# dual-h-bridge.net
KiCad netlist of a schematic drawn in EAGLE
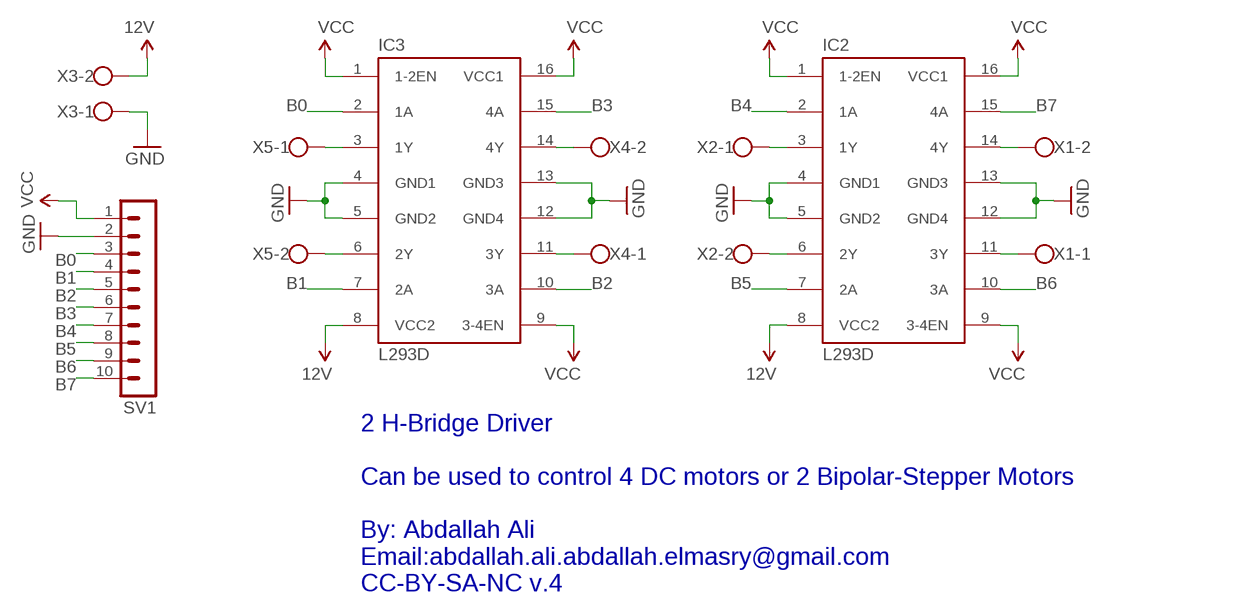
[diagram p0: schematic, sheet 1]

(export (version "E")
  (design (tool "Eeschema 10.0.6"))
  (components
    (comp (ref "IC2")
      (value "L293D")
      (footprint "eagle-import:DIL16")
      (libsource (lib "eagle-import") (part "L293D"))
    )
    (comp (ref "IC3")
      (value "L293D")
      (footprint "eagle-import:DIL16")
      (libsource (lib "eagle-import") (part "L293D"))
    )
    (comp (ref "SV1")
      (value "MA10-1")
      (footprint "eagle-import:MA10-1")
      (libsource (lib "eagle-import") (part "MA10-1"))
    )
    (comp (ref "X1")
      (value "W237-102")
      (footprint "eagle-import:W237-102")
      (fields (field (name "MPN") "237-102"))
      (libsource (lib "eagle-import") (part "W237-102"))
    )
    (comp (ref "X2")
      (value "W237-102")
      (footprint "eagle-import:W237-102")
      (fields (field (name "MPN") "237-102"))
      (libsource (lib "eagle-import") (part "W237-102"))
    )
    (comp (ref "X3")
      (value "W237-102")
      (footprint "eagle-import:W237-102")
      (fields (field (name "MPN") "237-102"))
      (libsource (lib "eagle-import") (part "W237-102"))
    )
    (comp (ref "X4")
      (value "W237-102")
      (footprint "eagle-import:W237-102")
      (fields (field (name "MPN") "237-102"))
      (libsource (lib "eagle-import") (part "W237-102"))
    )
    (comp (ref "X5")
      (value "W237-102")
      (footprint "eagle-import:W237-102")
      (fields (field (name "MPN") "237-102"))
      (libsource (lib "eagle-import") (part "W237-102"))
    )
  )
  (nets
    (net (code "1") (name "/B0") (class "Default")
      (node (ref "IC3") (pin "2") (pinfunction "1A_2") (pintype "input"))
      (node (ref "SV1") (pin "3") (pinfunction "3_3") (pintype "passive"))
    )
    (net (code "2") (name "/B1") (class "Default")
      (node (ref "IC3") (pin "7") (pinfunction "2A_7") (pintype "input"))
      (node (ref "SV1") (pin "4") (pinfunction "4_4") (pintype "passive"))
    )
    (net (code "3") (name "/B2") (class "Default")
      (node (ref "IC3") (pin "10") (pinfunction "3A_10") (pintype "input"))
      (node (ref "SV1") (pin "5") (pinfunction "5_5") (pintype "passive"))
    )
    (net (code "4") (name "/B3") (class "Default")
      (node (ref "IC3") (pin "15") (pinfunction "4A_15") (pintype "input"))
      (node (ref "SV1") (pin "6") (pinfunction "6_6") (pintype "passive"))
    )
    (net (code "5") (name "/B4") (class "Default")
      (node (ref "IC2") (pin "2") (pinfunction "1A_2") (pintype "input"))
      (node (ref "SV1") (pin "7") (pinfunction "7_7") (pintype "passive"))
    )
    (net (code "6") (name "/B5") (class "Default")
      (node (ref "IC2") (pin "7") (pinfunction "2A_7") (pintype "input"))
      (node (ref "SV1") (pin "8") (pinfunction "8_8") (pintype "passive"))
    )
    (net (code "7") (name "/B6") (class "Default")
      (node (ref "IC2") (pin "10") (pinfunction "3A_10") (pintype "input"))
      (node (ref "SV1") (pin "9") (pinfunction "9_9") (pintype "passive"))
    )
    (net (code "8") (name "/B7") (class "Default")
      (node (ref "IC2") (pin "15") (pinfunction "4A_15") (pintype "input"))
      (node (ref "SV1") (pin "10") (pinfunction "10_10") (pintype "passive"))
    )
    (net (code "9") (name "12V") (class "Default")
      (node (ref "IC2") (pin "8") (pinfunction "VCC2_8") (pintype "power_in"))
      (node (ref "IC3") (pin "8") (pinfunction "VCC2_8") (pintype "power_in"))
      (node (ref "X3") (pin "2") (pinfunction "KL_2") (pintype "passive"))
    )
    (net (code "10") (name "GND") (class "Default")
      (node (ref "IC2") (pin "12") (pinfunction "GND4_12") (pintype "power_in"))
      (node (ref "IC2") (pin "13") (pinfunction "GND3_13") (pintype "power_in"))
      (node (ref "IC2") (pin "4") (pinfunction "GND1_4") (pintype "power_in"))
      (node (ref "IC2") (pin "5") (pinfunction "GND2_5") (pintype "power_in"))
      (node (ref "IC3") (pin "12") (pinfunction "GND4_12") (pintype "power_in"))
      (node (ref "IC3") (pin "13") (pinfunction "GND3_13") (pintype "power_in"))
      (node (ref "IC3") (pin "4") (pinfunction "GND1_4") (pintype "power_in"))
      (node (ref "IC3") (pin "5") (pinfunction "GND2_5") (pintype "power_in"))
      (node (ref "SV1") (pin "2") (pinfunction "2_2") (pintype "passive"))
      (node (ref "X3") (pin "1") (pinfunction "KL_1") (pintype "passive"))
    )
    (net (code "11") (name "Net-(IC2-1Y)") (class "Default")
      (node (ref "IC2") (pin "3") (pinfunction "1Y_3") (pintype "output"))
      (node (ref "X2") (pin "1") (pinfunction "KL_1") (pintype "passive"))
    )
    (net (code "12") (name "Net-(IC2-2Y)") (class "Default")
      (node (ref "IC2") (pin "6") (pinfunction "2Y_6") (pintype "output"))
      (node (ref "X2") (pin "2") (pinfunction "KL_2") (pintype "passive"))
    )
    (net (code "13") (name "Net-(IC2-3Y)") (class "Default")
      (node (ref "IC2") (pin "11") (pinfunction "3Y_11") (pintype "output"))
      (node (ref "X1") (pin "1") (pinfunction "KL_1") (pintype "passive"))
    )
    (net (code "14") (name "Net-(IC2-4Y)") (class "Default")
      (node (ref "IC2") (pin "14") (pinfunction "4Y_14") (pintype "output"))
      (node (ref "X1") (pin "2") (pinfunction "KL_2") (pintype "passive"))
    )
    (net (code "15") (name "Net-(IC3-1Y)") (class "Default")
      (node (ref "IC3") (pin "3") (pinfunction "1Y_3") (pintype "output"))
      (node (ref "X5") (pin "1") (pinfunction "KL_1") (pintype "passive"))
    )
    (net (code "16") (name "Net-(IC3-2Y)") (class "Default")
      (node (ref "IC3") (pin "6") (pinfunction "2Y_6") (pintype "output"))
      (node (ref "X5") (pin "2") (pinfunction "KL_2") (pintype "passive"))
    )
    (net (code "17") (name "Net-(IC3-3Y)") (class "Default")
      (node (ref "IC3") (pin "11") (pinfunction "3Y_11") (pintype "output"))
      (node (ref "X4") (pin "1") (pinfunction "KL_1") (pintype "passive"))
    )
    (net (code "18") (name "Net-(IC3-4Y)") (class "Default")
      (node (ref "IC3") (pin "14") (pinfunction "4Y_14") (pintype "output"))
      (node (ref "X4") (pin "2") (pinfunction "KL_2") (pintype "passive"))
    )
    (net (code "19") (name "VCC") (class "Default")
      (node (ref "IC2") (pin "1") (pinfunction "1-2EN_1") (pintype "input"))
      (node (ref "IC2") (pin "16") (pinfunction "VCC1_16") (pintype "power_in"))
      (node (ref "IC2") (pin "9") (pinfunction "3-4EN_9") (pintype "input"))
      (node (ref "IC3") (pin "1") (pinfunction "1-2EN_1") (pintype "input"))
      (node (ref "IC3") (pin "16") (pinfunction "VCC1_16") (pintype "power_in"))
      (node (ref "IC3") (pin "9") (pinfunction "3-4EN_9") (pintype "input"))
      (node (ref "SV1") (pin "1") (pinfunction "1_1") (pintype "passive"))
    )
  )
)
